# basketball_robot_main_board_2018.net
KiCad netlist of a schematic drawn in Altium Designer
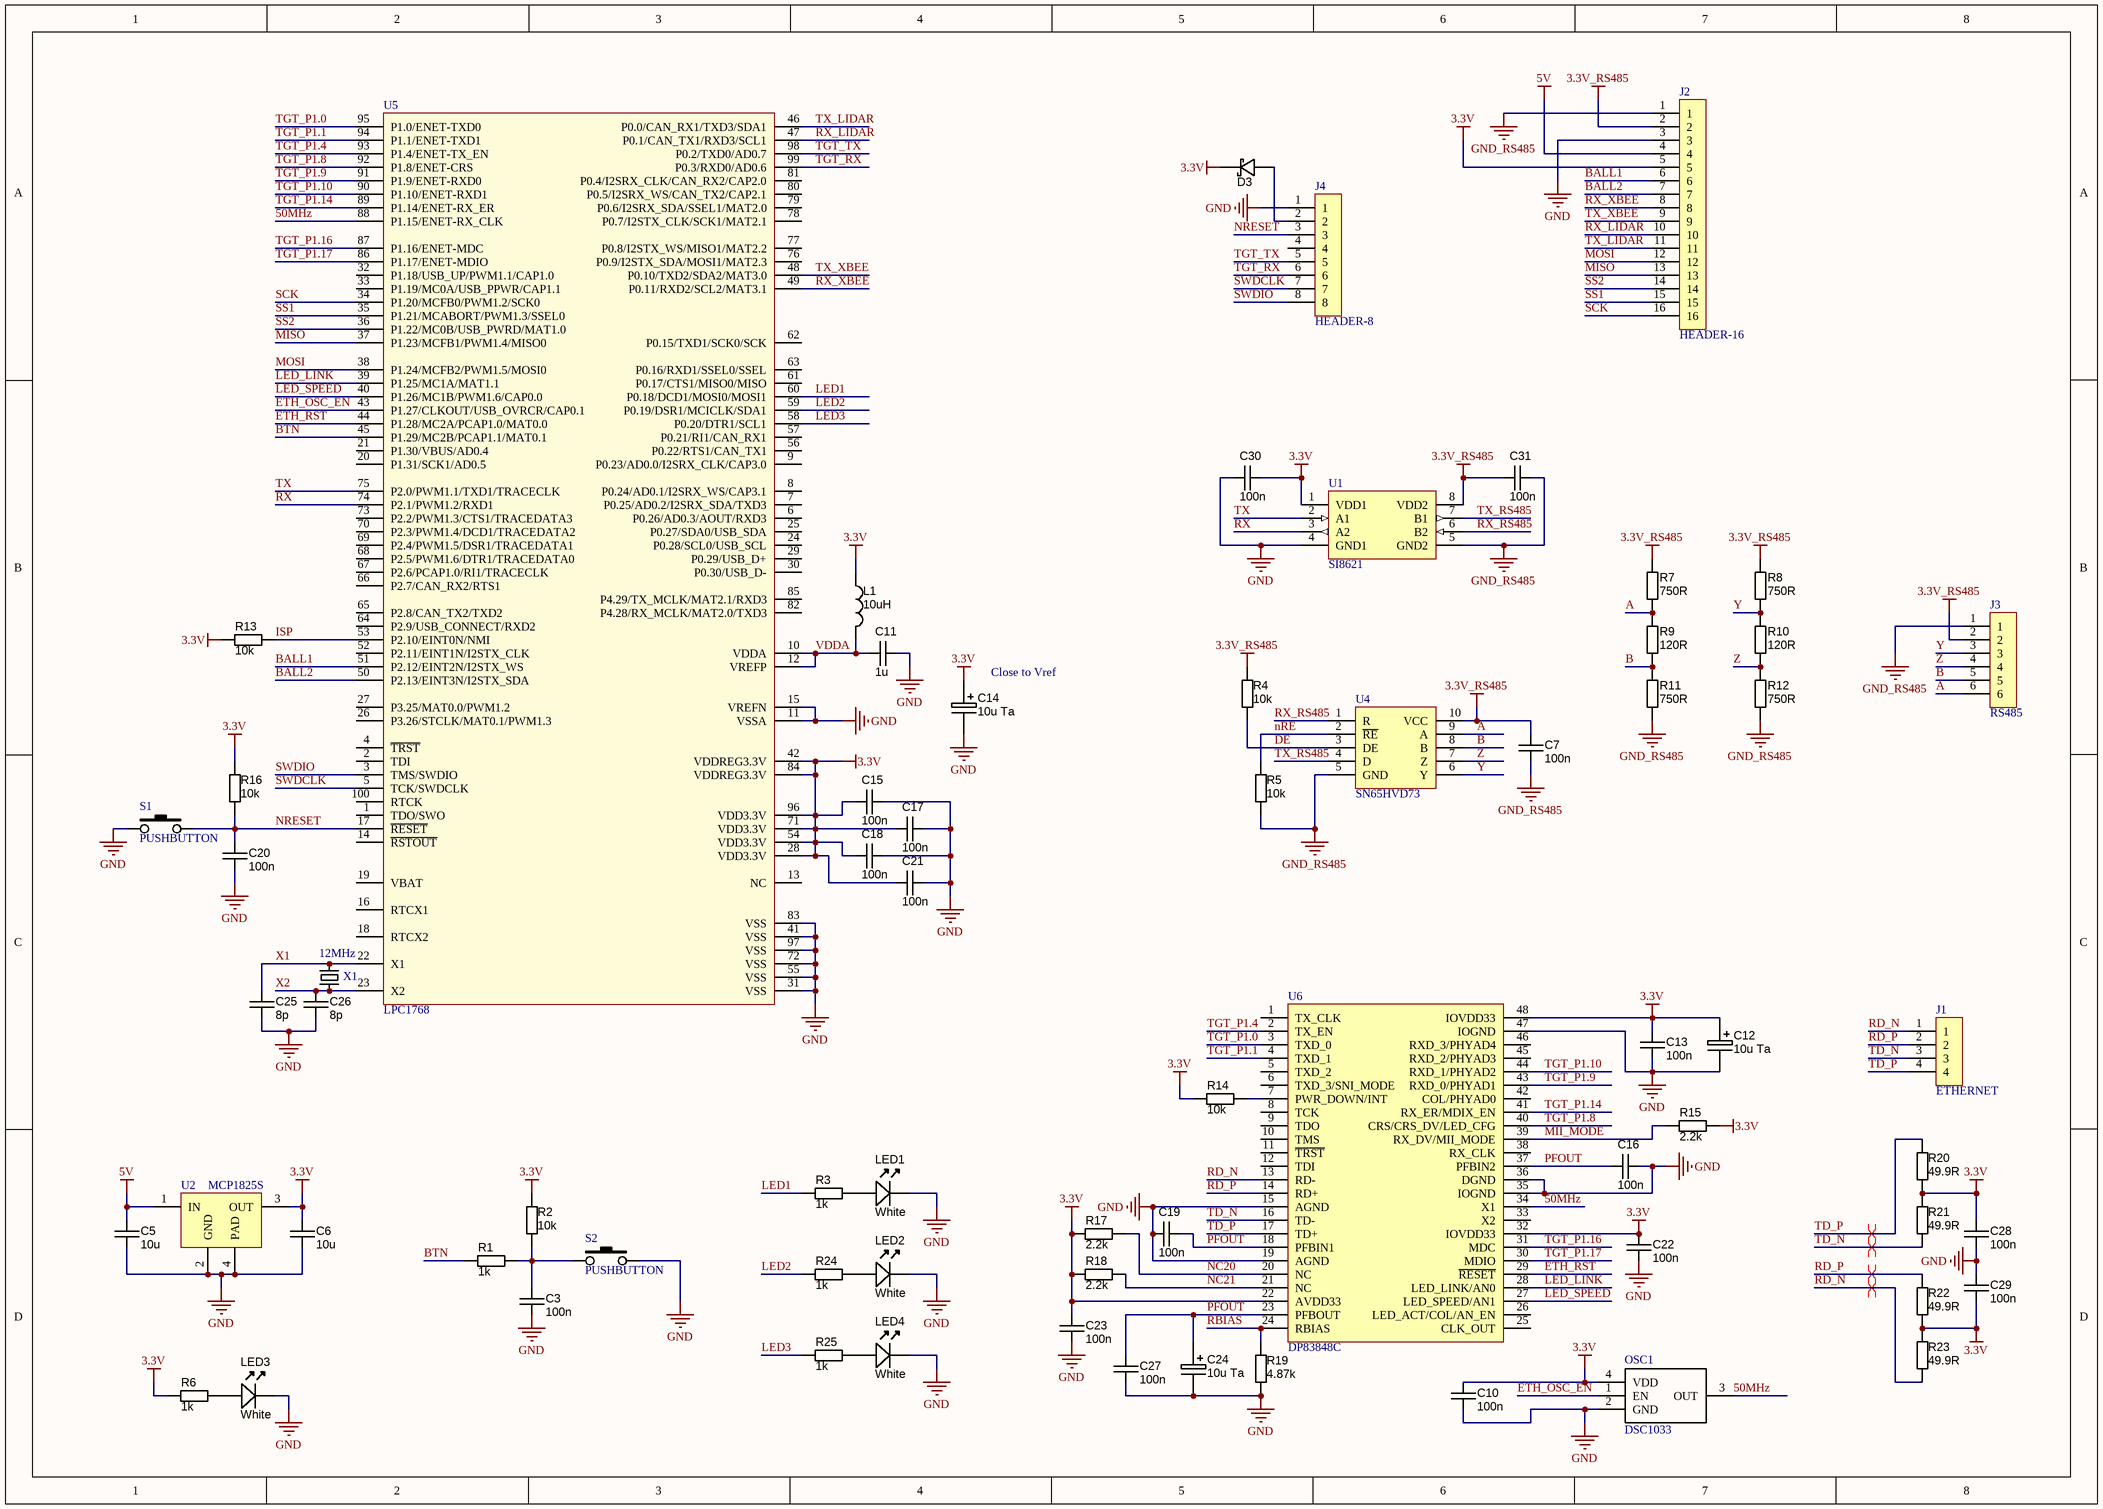
[diagram p0: basketball_robot_main_board_2018.SchDoc]

(export (version "E")
  (design (tool "Eeschema 10.0.6"))
  (components
    (comp (ref "C3")
      (value "100n")
      (footprint "CAPC1608X90N")
      (description "Capacitor SMD Cer 100nF 10% 50V X7R 0603")
      (fields (field (name "TOLERANCE") "±10%"))
      (libsource (lib "PBL - Capacitors") (part "CAPC_100n_0603_X7R_50V_10%"))
    )
    (comp (ref "C5")
      (value "10u")
      (footprint "CAPC3216X180N")
      (description "Capacitor SMD Cer 10uF 10% 10V X5R 1206")
      (fields (field (name "TOLERANCE") "±10%"))
      (libsource (lib "PBL - Capacitors") (part "CAPC_10u_1206_10V"))
    )
    (comp (ref "C6")
      (value "10u")
      (footprint "CAPC3216X180N")
      (description "Capacitor SMD Cer 10uF 10% 10V X5R 1206")
      (fields (field (name "TOLERANCE") "±10%"))
      (libsource (lib "PBL - Capacitors") (part "CAPC_10u_1206_10V"))
    )
    (comp (ref "C7")
      (value "100n")
      (footprint "CAPC1608X90N")
      (description "Capacitor SMD Cer 100nF 10% 50V X7R 0603")
      (fields (field (name "TOLERANCE") "±10%"))
      (libsource (lib "PBL - Capacitors") (part "CAPC_100n_0603_X7R_50V_10%"))
    )
    (comp (ref "C10")
      (value "100n")
      (footprint "CAPC1608X90N")
      (description "Capacitor SMD Cer 18pF 2% 100V NP0 0603")
      (fields (field (name "TOLERANCE") "±2%"))
      (libsource (lib "PBL - Capacitors") (part "CAPC_18p_0603_100V"))
    )
    (comp (ref "C11")
      (value "1u")
      (footprint "CAPC1608X90N")
      (description "Capacitor SMD Cer 1uF 10% 16V X7R 0603")
      (fields (field (name "TOLERANCE") "±10%"))
      (libsource (lib "PBL - Capacitors") (part "CAPC_1u_0603_X7R_16V_10%"))
    )
    (comp (ref "C12")
      (value "10u Ta")
      (footprint "CAPMP3528X210N")
      (description "Capacitor SMD Tantalum 47uF 20% 6.3V 1210")
      (fields (field (name "TOLERANCE") "±20%"))
      (libsource (lib "PBL - Capacitors") (part "CAPT_47u_1210_6V3"))
    )
    (comp (ref "C13")
      (value "100n")
      (footprint "CAPC1608X90N")
      (description "Capacitor SMD Cer 18pF 2% 100V NP0 0603")
      (fields (field (name "TOLERANCE") "±2%"))
      (libsource (lib "PBL - Capacitors") (part "CAPC_18p_0603_100V"))
    )
    (comp (ref "C14")
      (value "10u Ta")
      (footprint "CAPMP3528X210N")
      (description "Capacitor SMD Tantalum 47uF 20% 6.3V 1210")
      (fields (field (name "TOLERANCE") "±20%"))
      (libsource (lib "PBL - Capacitors") (part "CAPT_47u_1210_6V3"))
    )
    (comp (ref "C15")
      (value "100n")
      (footprint "CAPC1608X90N")
      (description "Capacitor SMD Cer 18pF 2% 100V NP0 0603")
      (fields (field (name "TOLERANCE") "±2%"))
      (libsource (lib "PBL - Capacitors") (part "CAPC_18p_0603_100V"))
    )
    (comp (ref "C16")
      (value "100n")
      (footprint "CAPC1608X90N")
      (description "Capacitor SMD Cer 18pF 2% 100V NP0 0603")
      (fields (field (name "TOLERANCE") "±2%"))
      (libsource (lib "PBL - Capacitors") (part "CAPC_18p_0603_100V"))
    )
    (comp (ref "C17")
      (value "100n")
      (footprint "CAPC1608X90N")
      (description "Capacitor SMD Cer 18pF 2% 100V NP0 0603")
      (fields (field (name "TOLERANCE") "±2%"))
      (libsource (lib "PBL - Capacitors") (part "CAPC_18p_0603_100V"))
    )
    (comp (ref "C18")
      (value "100n")
      (footprint "CAPC1608X90N")
      (description "Capacitor SMD Cer 18pF 2% 100V NP0 0603")
      (fields (field (name "TOLERANCE") "±2%"))
      (libsource (lib "PBL - Capacitors") (part "CAPC_18p_0603_100V"))
    )
    (comp (ref "C19")
      (value "100n")
      (footprint "CAPC1608X90N")
      (description "Capacitor SMD Cer 18pF 2% 100V NP0 0603")
      (fields (field (name "TOLERANCE") "±2%"))
      (libsource (lib "PBL - Capacitors") (part "CAPC_18p_0603_100V"))
    )
    (comp (ref "C20")
      (value "100n")
      (footprint "CAPC1608X90N")
      (description "Capacitor SMD Cer 18pF 2% 100V NP0 0603")
      (fields (field (name "TOLERANCE") "±2%"))
      (libsource (lib "PBL - Capacitors") (part "CAPC_18p_0603_100V"))
    )
    (comp (ref "C21")
      (value "100n")
      (footprint "CAPC1608X90N")
      (description "Capacitor SMD Cer 18pF 2% 100V NP0 0603")
      (fields (field (name "TOLERANCE") "±2%"))
      (libsource (lib "PBL - Capacitors") (part "CAPC_18p_0603_100V"))
    )
    (comp (ref "C22")
      (value "100n")
      (footprint "CAPC1608X90N")
      (description "Capacitor SMD Cer 18pF 2% 100V NP0 0603")
      (fields (field (name "TOLERANCE") "±2%"))
      (libsource (lib "PBL - Capacitors") (part "CAPC_18p_0603_100V"))
    )
    (comp (ref "C23")
      (value "100n")
      (footprint "CAPC1608X90N")
      (description "Capacitor SMD Cer 18pF 2% 100V NP0 0603")
      (fields (field (name "TOLERANCE") "±2%"))
      (libsource (lib "PBL - Capacitors") (part "CAPC_18p_0603_100V"))
    )
    (comp (ref "C24")
      (value "10u Ta")
      (footprint "CAPMP3528X210N")
      (description "Capacitor SMD Tantalum 47uF 20% 6.3V 1210")
      (fields (field (name "TOLERANCE") "±20%"))
      (libsource (lib "PBL - Capacitors") (part "CAPT_47u_1210_6V3"))
    )
    (comp (ref "C25")
      (value "8p")
      (footprint "CAPC1608X90N")
      (description "Capacitor SMD Cer 18pF 2% 100V NP0 0603")
      (fields (field (name "TOLERANCE") "±2%"))
      (libsource (lib "PBL - Capacitors") (part "CAPC_18p_0603_100V"))
    )
    (comp (ref "C26")
      (value "8p")
      (footprint "CAPC1608X90N")
      (description "Capacitor SMD Cer 18pF 2% 100V NP0 0603")
      (fields (field (name "TOLERANCE") "±2%"))
      (libsource (lib "PBL - Capacitors") (part "CAPC_18p_0603_100V"))
    )
    (comp (ref "C27")
      (value "100n")
      (footprint "CAPC1608X90N")
      (description "Capacitor SMD Cer 18pF 2% 100V NP0 0603")
      (fields (field (name "TOLERANCE") "±2%"))
      (libsource (lib "PBL - Capacitors") (part "CAPC_18p_0603_100V"))
    )
    (comp (ref "C28")
      (value "100n")
      (footprint "CAPC1608X90N")
      (description "Capacitor SMD Cer 18pF 2% 100V NP0 0603")
      (fields (field (name "TOLERANCE") "±2%"))
      (libsource (lib "PBL - Capacitors") (part "CAPC_18p_0603_100V"))
    )
    (comp (ref "C29")
      (value "100n")
      (footprint "CAPC1608X90N")
      (description "Capacitor SMD Cer 18pF 2% 100V NP0 0603")
      (fields (field (name "TOLERANCE") "±2%"))
      (libsource (lib "PBL - Capacitors") (part "CAPC_18p_0603_100V"))
    )
    (comp (ref "C30")
      (value "100n")
      (footprint "CAPC1608X90N")
      (description "Capacitor SMD Cer 100nF 10% 50V X7R 0603")
      (fields (field (name "TOLERANCE") "±10%"))
      (libsource (lib "PBL - Capacitors") (part "CAPC_100n_0603_X7R_50V_10%"))
    )
    (comp (ref "C31")
      (value "100n")
      (footprint "CAPC1608X90N")
      (description "Capacitor SMD Cer 100nF 10% 50V X7R 0603")
      (fields (field (name "TOLERANCE") "±10%"))
      (libsource (lib "PBL - Capacitors") (part "CAPC_100n_0603_X7R_50V_10%"))
    )
    (comp (ref "D3")
      (value "~")
      (footprint "SOD323")
      (description "Diode Schottky SMD 20V 0.5A SOD123")
      (libsource (lib "PBL - Diodes") (part "DIODE_SCHOTTKY_SS0520"))
    )
    (comp (ref "J1")
      (value "ETHERNET")
      (footprint "MICRO-MATCH-FOB-04")
      (libsource (lib "connectors_micromatch") (part "HEADER-4"))
    )
    (comp (ref "J2")
      (value "HEADER-16")
      (footprint "MICRO-MATCH-FOB-SMD-16")
      (libsource (lib "connectors_micromatch") (part "HEADER-16"))
    )
    (comp (ref "J3")
      (value "RS485")
      (footprint "MICRO-MATCH-FOB-06")
      (libsource (lib "connectors_micromatch") (part "HEADER-6"))
    )
    (comp (ref "J4")
      (value "HEADER-8")
      (footprint "MICRO-MATCH-FOB-SMD-08")
      (libsource (lib "connectors_micromatch") (part "HEADER-8"))
    )
    (comp (ref "L1")
      (value "10uH")
      (footprint "INDC1608N")
      (description "Ferrite bead 120 Ohm at 100 MHz 2A 0603 SMD")
      (libsource (lib "PBL - Inductors") (part "FERRITE_120R-100MHz_0603"))
    )
    (comp (ref "LED1")
      (value "White")
      (footprint "LED-0603-WHITE")
      (description "LED 0603 SMD Bright White 8700K")
      (libsource (lib "PBL - Light Sources") (part "LED_SMD_White_0603_Bright"))
    )
    (comp (ref "LED2")
      (value "White")
      (footprint "LED-0603-WHITE")
      (description "LED 0603 SMD Bright White 8700K")
      (libsource (lib "PBL - Light Sources") (part "LED_SMD_White_0603_Bright"))
    )
    (comp (ref "LED3")
      (value "White")
      (footprint "LED-0603-WHITE")
      (description "LED 0603 SMD Bright White 8700K")
      (libsource (lib "PBL - Light Sources") (part "LED_SMD_White_0603_Bright"))
    )
    (comp (ref "LED4")
      (value "White")
      (footprint "LED-0603-WHITE")
      (description "LED 0603 SMD Bright White 8700K")
      (libsource (lib "PBL - Light Sources") (part "LED_SMD_White_0603_Bright"))
    )
    (comp (ref "OSC1")
      (value "DSC1033")
      (footprint "DSC1033-3.2x2.5")
      (libsource (lib "misc") (part "DSC1033"))
    )
    (comp (ref "R1")
      (value "1k")
      (footprint "RESC1608X55N")
      (description "Resistor SMD chip 120 Ohm 0.1W 5% 0603")
      (fields (field (name "TOLERANCE") "±5%"))
      (libsource (lib "") (part "RES_120R_0603_5%_1"))
    )
    (comp (ref "R2")
      (value "10k")
      (footprint "RESC1608X55N")
      (description "Resistor SMD chip 120 Ohm 0.1W 5% 0603")
      (fields (field (name "TOLERANCE") "±5%"))
      (libsource (lib "") (part "RES_120R_0603_5%_2"))
    )
    (comp (ref "R3")
      (value "1k")
      (footprint "RESC1608X55N")
      (description "Resistor SMD chip 120 Ohm 0.1W 5% 0603")
      (fields (field (name "TOLERANCE") "±5%"))
      (libsource (lib "") (part "RES_120R_0603_5%_1"))
    )
    (comp (ref "R4")
      (value "10k")
      (footprint "RESC1608X55N")
      (description "Resistor SMD chip 120 Ohm 0.1W 5% 0603")
      (fields (field (name "TOLERANCE") "±5%"))
      (libsource (lib "") (part "RES_120R_0603_5%_2"))
    )
    (comp (ref "R5")
      (value "10k")
      (footprint "RESC1608X55N")
      (description "Resistor SMD chip 120 Ohm 0.1W 5% 0603")
      (fields (field (name "TOLERANCE") "±5%"))
      (libsource (lib "") (part "RES_120R_0603_5%_2"))
    )
    (comp (ref "R6")
      (value "1k")
      (footprint "RESC1608X55N")
      (description "Resistor SMD chip 120 Ohm 0.1W 5% 0603")
      (fields (field (name "TOLERANCE") "±5%"))
      (libsource (lib "") (part "RES_120R_0603_5%_1"))
    )
    (comp (ref "R7")
      (value "750R")
      (footprint "RESC1608X55N")
      (description "Resistor SMD chip 120 Ohm 0.1W 5% 0603")
      (fields (field (name "TOLERANCE") "±5%"))
      (libsource (lib "PBL - Resistors") (part "RES_120R_0603_5%"))
    )
    (comp (ref "R8")
      (value "750R")
      (footprint "RESC1608X55N")
      (description "Resistor SMD chip 120 Ohm 0.1W 5% 0603")
      (fields (field (name "TOLERANCE") "±5%"))
      (libsource (lib "PBL - Resistors") (part "RES_120R_0603_5%"))
    )
    (comp (ref "R9")
      (value "120R")
      (footprint "RESC1608X55N")
      (description "Resistor SMD chip 120 Ohm 0.1W 5% 0603")
      (fields (field (name "TOLERANCE") "±5%"))
      (libsource (lib "PBL - Resistors") (part "RES_120R_0603_5%"))
    )
    (comp (ref "R10")
      (value "120R")
      (footprint "RESC1608X55N")
      (description "Resistor SMD chip 120 Ohm 0.1W 5% 0603")
      (fields (field (name "TOLERANCE") "±5%"))
      (libsource (lib "PBL - Resistors") (part "RES_120R_0603_5%"))
    )
    (comp (ref "R11")
      (value "750R")
      (footprint "RESC1608X55N")
      (description "Resistor SMD chip 120 Ohm 0.1W 5% 0603")
      (fields (field (name "TOLERANCE") "±5%"))
      (libsource (lib "PBL - Resistors") (part "RES_120R_0603_5%"))
    )
    (comp (ref "R12")
      (value "750R")
      (footprint "RESC1608X55N")
      (description "Resistor SMD chip 120 Ohm 0.1W 5% 0603")
      (fields (field (name "TOLERANCE") "±5%"))
      (libsource (lib "PBL - Resistors") (part "RES_120R_0603_5%"))
    )
    (comp (ref "R13")
      (value "10k")
      (footprint "RESC1608X55N")
      (description "Resistor SMD chip 10k Ohm 0.1W 5% 0603")
      (fields (field (name "TOLERANCE") "±5%"))
      (libsource (lib "") (part "RES_10K_0603_5%_1"))
    )
    (comp (ref "R14")
      (value "10k")
      (footprint "RESC1608X55N")
      (description "Resistor SMD chip 10k Ohm 0.1W 5% 0603")
      (fields (field (name "TOLERANCE") "±5%"))
      (libsource (lib "") (part "RES_10K_0603_5%_1"))
    )
    (comp (ref "R15")
      (value "2.2k")
      (footprint "RESC1608X55N")
      (description "Resistor SMD chip 10k Ohm 0.1W 5% 0603")
      (fields (field (name "TOLERANCE") "±5%"))
      (libsource (lib "") (part "RES_10K_0603_5%_1"))
    )
    (comp (ref "R16")
      (value "10k")
      (footprint "RESC1608X55N")
      (description "Resistor SMD chip 10k Ohm 0.1W 5% 0603")
      (fields (field (name "TOLERANCE") "±5%"))
      (libsource (lib "PBL - Resistors") (part "RES_10K_0603_5%"))
    )
    (comp (ref "R17")
      (value "2.2k")
      (footprint "RESC1608X55N")
      (description "Resistor SMD chip 10k Ohm 0.1W 5% 0603")
      (fields (field (name "TOLERANCE") "±5%"))
      (libsource (lib "") (part "RES_10K_0603_5%_1"))
    )
    (comp (ref "R18")
      (value "2.2k")
      (footprint "RESC1608X55N")
      (description "Resistor SMD chip 10k Ohm 0.1W 5% 0603")
      (fields (field (name "TOLERANCE") "±5%"))
      (libsource (lib "") (part "RES_10K_0603_5%_1"))
    )
    (comp (ref "R19")
      (value "4.87k")
      (footprint "RESC1608X55N")
      (description "Resistor SMD chip 10k Ohm 0.1W 5% 0603")
      (fields (field (name "TOLERANCE") "±5%"))
      (libsource (lib "PBL - Resistors") (part "RES_10K_0603_5%"))
    )
    (comp (ref "R20")
      (value "49.9R")
      (footprint "RESC1608X55N")
      (description "Resistor SMD chip 10k Ohm 0.1W 5% 0603")
      (fields (field (name "TOLERANCE") "±5%"))
      (libsource (lib "PBL - Resistors") (part "RES_10K_0603_5%"))
    )
    (comp (ref "R21")
      (value "49.9R")
      (footprint "RESC1608X55N")
      (description "Resistor SMD chip 10k Ohm 0.1W 5% 0603")
      (fields (field (name "TOLERANCE") "±5%"))
      (libsource (lib "PBL - Resistors") (part "RES_10K_0603_5%"))
    )
    (comp (ref "R22")
      (value "49.9R")
      (footprint "RESC1608X55N")
      (description "Resistor SMD chip 10k Ohm 0.1W 5% 0603")
      (fields (field (name "TOLERANCE") "±5%"))
      (libsource (lib "PBL - Resistors") (part "RES_10K_0603_5%"))
    )
    (comp (ref "R23")
      (value "49.9R")
      (footprint "RESC1608X55N")
      (description "Resistor SMD chip 10k Ohm 0.1W 5% 0603")
      (fields (field (name "TOLERANCE") "±5%"))
      (libsource (lib "PBL - Resistors") (part "RES_10K_0603_5%"))
    )
    (comp (ref "R24")
      (value "1k")
      (footprint "RESC1608X55N")
      (description "Resistor SMD chip 120 Ohm 0.1W 5% 0603")
      (fields (field (name "TOLERANCE") "±5%"))
      (libsource (lib "") (part "RES_120R_0603_5%_1"))
    )
    (comp (ref "R25")
      (value "1k")
      (footprint "RESC1608X55N")
      (description "Resistor SMD chip 120 Ohm 0.1W 5% 0603")
      (fields (field (name "TOLERANCE") "±5%"))
      (libsource (lib "") (part "RES_120R_0603_5%_1"))
    )
    (comp (ref "S1")
      (value "PUSHBUTTON")
      (footprint "KMR421NGLFS")
      (libsource (lib "switches") (part "PUSHBUTTON"))
    )
    (comp (ref "S2")
      (value "PUSHBUTTON")
      (footprint "NKK_AB11AP-FA")
      (libsource (lib "switches") (part "PUSHBUTTON"))
    )
    (comp (ref "U1") (value "SI8621") (footprint "SOIC8") (libsource (lib "digital") (part "SI8621")))
    (comp (ref "U2")
      (value "MCP1825S")
      (footprint "SOT230P700X180-4N")
      (libsource (lib "power") (part "MIC5239"))
    )
    (comp (ref "U4")
      (value "SN65HVD73")
      (footprint "SOP10")
      (libsource (lib "texas_instruments") (part "SN65HVD3086E"))
    )
    (comp (ref "U5") (value "LPC1768") (footprint "LQFP100") (libsource (lib "nxp") (part "LPC1768")))
    (comp (ref "U6")
      (value "DP83848C")
      (footprint "PQFP48")
      (libsource (lib "texas_instruments") (part "DP83848C"))
    )
    (comp (ref "X1")
      (value "12MHz")
      (footprint "XTAL-3.2x2.5")
      (libsource (lib "misc") (part "XTAL-3.2X2.5"))
    )
  )
  (nets
    (net (code "1") (name "/50MHz") (class "Default")
      (node (ref "OSC1") (pin "3") (pinfunction "OUT_3") (pintype "passive"))
      (node (ref "U5") (pin "88") (pinfunction "P1.15/ENET-RX_CLK_88") (pintype "passive"))
      (node (ref "U6") (pin "34") (pinfunction "X1_34") (pintype "passive"))
    )
    (net (code "2") (name "/A") (class "Default")
      (node (ref "J3") (pin "6") (pinfunction "6_6") (pintype "passive"))
      (node (ref "R7") (pin "2") (pinfunction "2_2") (pintype "passive"))
      (node (ref "R9") (pin "1") (pinfunction "1_1") (pintype "passive"))
      (node (ref "U4") (pin "9") (pinfunction "A_9") (pintype "passive"))
    )
    (net (code "3") (name "/B") (class "Default")
      (node (ref "J3") (pin "5") (pinfunction "5_5") (pintype "passive"))
      (node (ref "R11") (pin "1") (pinfunction "1_1") (pintype "passive"))
      (node (ref "R9") (pin "2") (pinfunction "2_2") (pintype "passive"))
      (node (ref "U4") (pin "8") (pinfunction "B_8") (pintype "passive"))
    )
    (net (code "4") (name "/BALL1") (class "Default")
      (node (ref "J2") (pin "6") (pinfunction "6_6") (pintype "passive"))
      (node (ref "U5") (pin "51") (pinfunction "P2.12/EINT2N/I2STX_WS_51") (pintype "passive"))
    )
    (net (code "5") (name "/BALL2") (class "Default")
      (node (ref "J2") (pin "7") (pinfunction "7_7") (pintype "passive"))
      (node (ref "U5") (pin "50") (pinfunction "P2.13/EINT3N/I2STX_SDA_50") (pintype "passive"))
    )
    (net (code "6") (name "/BTN") (class "Default")
      (node (ref "R1") (pin "2") (pinfunction "2_2") (pintype "passive"))
      (node (ref "U5") (pin "45") (pinfunction "P1.29/MC2B/PCAP1.1/MAT0.1_45") (pintype "passive"))
    )
    (net (code "7") (name "/DE") (class "Default")
      (node (ref "R4") (pin "1") (pinfunction "1_1") (pintype "passive"))
      (node (ref "U4") (pin "3") (pinfunction "DE_3") (pintype "passive"))
    )
    (net (code "8") (name "/ETH_OSC_EN") (class "Default")
      (node (ref "OSC1") (pin "1") (pinfunction "EN_1") (pintype "passive"))
      (node (ref "U5") (pin "43") (pinfunction "P1.27/CLKOUT/USB_OVRCR/CAP0.1_43") (pintype "passive"))
    )
    (net (code "9") (name "/ETH_RST") (class "Default")
      (node (ref "U5") (pin "44") (pinfunction "P1.28/MC2A/PCAP1.0/MAT0.0_44") (pintype "passive"))
      (node (ref "U6") (pin "29") (pinfunction "~{RESET}_29") (pintype "passive"))
    )
    (net (code "10") (name "/ISP") (class "Default")
      (node (ref "R13") (pin "1") (pinfunction "1_1") (pintype "passive"))
      (node (ref "U5") (pin "53") (pinfunction "P2.10/EINT0N/NMI_53") (pintype "passive"))
    )
    (net (code "11") (name "/LED1") (class "Default")
      (node (ref "R3") (pin "2") (pinfunction "2_2") (pintype "passive"))
      (node (ref "U5") (pin "60") (pinfunction "P0.18/DCD1/MOSI0/MOSI1_60") (pintype "passive"))
    )
    (net (code "12") (name "/LED2") (class "Default")
      (node (ref "R24") (pin "2") (pinfunction "2_2") (pintype "passive"))
      (node (ref "U5") (pin "59") (pinfunction "P0.19/DSR1/MCICLK/SDA1_59") (pintype "passive"))
    )
    (net (code "13") (name "/LED3") (class "Default")
      (node (ref "R25") (pin "2") (pinfunction "2_2") (pintype "passive"))
      (node (ref "U5") (pin "58") (pinfunction "P0.20/DTR1/SCL1_58") (pintype "passive"))
    )
    (net (code "14") (name "/LED_LINK") (class "Default")
      (node (ref "U5") (pin "39") (pinfunction "P1.25/MC1A/MAT1.1_39") (pintype "passive"))
      (node (ref "U6") (pin "28") (pinfunction "LED_LINK/AN0_28") (pintype "passive"))
    )
    (net (code "15") (name "/LED_SPEED") (class "Default")
      (node (ref "U5") (pin "40") (pinfunction "P1.26/MC1B/PWM1.6/CAP0.0_40") (pintype "passive"))
      (node (ref "U6") (pin "27") (pinfunction "LED_SPEED/AN1_27") (pintype "passive"))
    )
    (net (code "16") (name "/MII_MODE") (class "Default")
      (node (ref "R15") (pin "2") (pinfunction "2_2") (pintype "passive"))
      (node (ref "U6") (pin "39") (pinfunction "RX_DV/MII_MODE_39") (pintype "passive"))
    )
    (net (code "17") (name "/MISO") (class "Default")
      (node (ref "J2") (pin "13") (pinfunction "13_13") (pintype "passive"))
      (node (ref "U5") (pin "37") (pinfunction "P1.23/MCFB1/PWM1.4/MISO0_37") (pintype "passive"))
    )
    (net (code "18") (name "/MOSI") (class "Default")
      (node (ref "J2") (pin "12") (pinfunction "12_12") (pintype "passive"))
      (node (ref "U5") (pin "38") (pinfunction "P1.24/MCFB2/PWM1.5/MOSI0_38") (pintype "passive"))
    )
    (net (code "19") (name "/NC20") (class "Default")
      (node (ref "R17") (pin "1") (pinfunction "1_1") (pintype "passive"))
      (node (ref "U6") (pin "20") (pinfunction "NC_20") (pintype "passive"))
    )
    (net (code "20") (name "/NC21") (class "Default")
      (node (ref "R18") (pin "1") (pinfunction "1_1") (pintype "passive"))
      (node (ref "U6") (pin "21") (pinfunction "NC_21") (pintype "passive"))
    )
    (net (code "21") (name "/NRESET") (class "Default")
      (node (ref "C20") (pin "1") (pintype "passive"))
      (node (ref "J4") (pin "3") (pinfunction "3_3") (pintype "passive"))
      (node (ref "R16") (pin "2") (pinfunction "2_2") (pintype "passive"))
      (node (ref "S1") (pin "2") (pintype "passive"))
      (node (ref "U5") (pin "17") (pinfunction "~{RESET}_17") (pintype "passive"))
    )
    (net (code "22") (name "/PFOUT") (class "Default")
      (node (ref "C16") (pin "1") (pintype "passive"))
      (node (ref "C19") (pin "2") (pintype "passive"))
      (node (ref "C24") (pin "1") (pintype "passive"))
      (node (ref "C27") (pin "2") (pintype "passive"))
      (node (ref "U6") (pin "18") (pinfunction "PFBIN1_18") (pintype "passive"))
      (node (ref "U6") (pin "23") (pinfunction "PFBOUT_23") (pintype "passive"))
      (node (ref "U6") (pin "37") (pinfunction "PFBIN2_37") (pintype "passive"))
    )
    (net (code "23") (name "/RBIAS") (class "Default")
      (node (ref "R19") (pin "1") (pinfunction "1_1") (pintype "passive"))
      (node (ref "U6") (pin "24") (pinfunction "RBIAS_24") (pintype "passive"))
    )
    (net (code "24") (name "/RD_N") (class "Default")
      (node (ref "J1") (pin "1") (pinfunction "1_1") (pintype "passive"))
      (node (ref "R23") (pin "2") (pinfunction "2_2") (pintype "passive"))
      (node (ref "U6") (pin "13") (pinfunction "RD-_13") (pintype "passive"))
    )
    (net (code "25") (name "/RD_P") (class "Default")
      (node (ref "J1") (pin "2") (pinfunction "2_2") (pintype "passive"))
      (node (ref "R22") (pin "1") (pinfunction "1_1") (pintype "passive"))
      (node (ref "U6") (pin "14") (pinfunction "RD+_14") (pintype "passive"))
    )
    (net (code "26") (name "/RX") (class "Default")
      (node (ref "U1") (pin "3") (pinfunction "A2_3") (pintype "output"))
      (node (ref "U5") (pin "74") (pinfunction "P2.1/PWM1.2/RXD1_74") (pintype "passive"))
    )
    (net (code "27") (name "/RX_LIDAR") (class "Default")
      (node (ref "J2") (pin "10") (pinfunction "10_10") (pintype "passive"))
      (node (ref "U5") (pin "47") (pinfunction "P0.1/CAN_TX1/RXD3/SCL1_47") (pintype "passive"))
    )
    (net (code "28") (name "/RX_RS485") (class "Default")
      (node (ref "U1") (pin "6") (pinfunction "B2_6") (pintype "input"))
      (node (ref "U4") (pin "1") (pinfunction "R_1") (pintype "passive"))
    )
    (net (code "29") (name "/RX_XBEE") (class "Default")
      (node (ref "J2") (pin "8") (pinfunction "8_8") (pintype "passive"))
      (node (ref "U5") (pin "49") (pinfunction "P0.11/RXD2/SCL2/MAT3.1_49") (pintype "passive"))
    )
    (net (code "30") (name "/SCK") (class "Default")
      (node (ref "J2") (pin "16") (pinfunction "16_16") (pintype "passive"))
      (node (ref "U5") (pin "34") (pinfunction "P1.20/MCFB0/PWM1.2/SCK0_34") (pintype "passive"))
    )
    (net (code "31") (name "/SS1") (class "Default")
      (node (ref "J2") (pin "15") (pinfunction "15_15") (pintype "passive"))
      (node (ref "U5") (pin "35") (pinfunction "P1.21/MCABORT/PWM1.3/SSEL0_35") (pintype "passive"))
    )
    (net (code "32") (name "/SS2") (class "Default")
      (node (ref "J2") (pin "14") (pinfunction "14_14") (pintype "passive"))
      (node (ref "U5") (pin "36") (pinfunction "P1.22/MC0B/USB_PWRD/MAT1.0_36") (pintype "passive"))
    )
    (net (code "33") (name "/SWDCLK") (class "Default")
      (node (ref "J4") (pin "7") (pinfunction "7_7") (pintype "passive"))
      (node (ref "U5") (pin "5") (pinfunction "TCK/SWDCLK_5") (pintype "passive"))
    )
    (net (code "34") (name "/SWDIO") (class "Default")
      (node (ref "J4") (pin "8") (pinfunction "8_8") (pintype "passive"))
      (node (ref "U5") (pin "3") (pinfunction "TMS/SWDIO_3") (pintype "passive"))
    )
    (net (code "35") (name "/TD_N") (class "Default")
      (node (ref "J1") (pin "3") (pinfunction "3_3") (pintype "passive"))
      (node (ref "R21") (pin "2") (pinfunction "2_2") (pintype "passive"))
      (node (ref "U6") (pin "16") (pinfunction "TD-_16") (pintype "passive"))
    )
    (net (code "36") (name "/TD_P") (class "Default")
      (node (ref "J1") (pin "4") (pinfunction "4_4") (pintype "passive"))
      (node (ref "R20") (pin "1") (pinfunction "1_1") (pintype "passive"))
      (node (ref "U6") (pin "17") (pinfunction "TD+_17") (pintype "passive"))
    )
    (net (code "37") (name "/TGT_P1.0") (class "Default")
      (node (ref "U5") (pin "95") (pinfunction "P1.0/ENET-TXD0_95") (pintype "passive"))
      (node (ref "U6") (pin "3") (pinfunction "TXD_0_3") (pintype "passive"))
    )
    (net (code "38") (name "/TGT_P1.1") (class "Default")
      (node (ref "U5") (pin "94") (pinfunction "P1.1/ENET-TXD1_94") (pintype "passive"))
      (node (ref "U6") (pin "4") (pinfunction "TXD_1_4") (pintype "passive"))
    )
    (net (code "39") (name "/TGT_P1.4") (class "Default")
      (node (ref "U5") (pin "93") (pinfunction "P1.4/ENET-TX_EN_93") (pintype "passive"))
      (node (ref "U6") (pin "2") (pinfunction "TX_EN_2") (pintype "passive"))
    )
    (net (code "40") (name "/TGT_P1.8") (class "Default")
      (node (ref "U5") (pin "92") (pinfunction "P1.8/ENET-CRS_92") (pintype "passive"))
      (node (ref "U6") (pin "40") (pinfunction "CRS/CRS_DV/LED_CFG_40") (pintype "passive"))
    )
    (net (code "41") (name "/TGT_P1.9") (class "Default")
      (node (ref "U5") (pin "91") (pinfunction "P1.9/ENET-RXD0_91") (pintype "passive"))
      (node (ref "U6") (pin "43") (pinfunction "RXD_0/PHYAD1_43") (pintype "passive"))
    )
    (net (code "42") (name "/TGT_P1.10") (class "Default")
      (node (ref "U5") (pin "90") (pinfunction "P1.10/ENET-RXD1_90") (pintype "passive"))
      (node (ref "U6") (pin "44") (pinfunction "RXD_1/PHYAD2_44") (pintype "passive"))
    )
    (net (code "43") (name "/TGT_P1.14") (class "Default")
      (node (ref "U5") (pin "89") (pinfunction "P1.14/ENET-RX_ER_89") (pintype "passive"))
      (node (ref "U6") (pin "41") (pinfunction "RX_ER/MDIX_EN_41") (pintype "passive"))
    )
    (net (code "44") (name "/TGT_P1.16") (class "Default")
      (node (ref "U5") (pin "87") (pinfunction "P1.16/ENET-MDC_87") (pintype "passive"))
      (node (ref "U6") (pin "31") (pinfunction "MDC_31") (pintype "passive"))
    )
    (net (code "45") (name "/TGT_P1.17") (class "Default")
      (node (ref "U5") (pin "86") (pinfunction "P1.17/ENET-MDIO_86") (pintype "passive"))
      (node (ref "U6") (pin "30") (pinfunction "MDIO_30") (pintype "passive"))
    )
    (net (code "46") (name "/TGT_RX") (class "Default")
      (node (ref "J4") (pin "6") (pinfunction "6_6") (pintype "passive"))
      (node (ref "U5") (pin "99") (pinfunction "P0.3/RXD0/AD0.6_99") (pintype "passive"))
    )
    (net (code "47") (name "/TGT_TX") (class "Default")
      (node (ref "J4") (pin "5") (pinfunction "5_5") (pintype "passive"))
      (node (ref "U5") (pin "98") (pinfunction "P0.2/TXD0/AD0.7_98") (pintype "passive"))
    )
    (net (code "48") (name "/TX") (class "Default")
      (node (ref "U1") (pin "2") (pinfunction "A1_2") (pintype "input"))
      (node (ref "U5") (pin "75") (pinfunction "P2.0/PWM1.1/TXD1/TRACECLK_75") (pintype "passive"))
    )
    (net (code "49") (name "/TX_LIDAR") (class "Default")
      (node (ref "J2") (pin "11") (pinfunction "11_11") (pintype "passive"))
      (node (ref "U5") (pin "46") (pinfunction "P0.0/CAN_RX1/TXD3/SDA1_46") (pintype "passive"))
    )
    (net (code "50") (name "/TX_RS485") (class "Default")
      (node (ref "U1") (pin "7") (pinfunction "B1_7") (pintype "output"))
      (node (ref "U4") (pin "4") (pinfunction "D_4") (pintype "passive"))
    )
    (net (code "51") (name "/TX_XBEE") (class "Default")
      (node (ref "J2") (pin "9") (pinfunction "9_9") (pintype "passive"))
      (node (ref "U5") (pin "48") (pinfunction "P0.10/TXD2/SDA2/MAT3.0_48") (pintype "passive"))
    )
    (net (code "52") (name "/VDDA") (class "Default")
      (node (ref "C11") (pin "1") (pintype "passive"))
      (node (ref "L1") (pin "2") (pinfunction "2_2") (pintype "passive"))
      (node (ref "U5") (pin "10") (pinfunction "VDDA_10") (pintype "passive"))
      (node (ref "U5") (pin "12") (pinfunction "VREFP_12") (pintype "passive"))
    )
    (net (code "53") (name "/X1") (class "Default")
      (node (ref "C25") (pin "1") (pintype "passive"))
      (node (ref "U5") (pin "22") (pinfunction "X1_22") (pintype "passive"))
      (node (ref "X1") (pin "3") (pinfunction "3_3") (pintype "passive"))
    )
    (net (code "54") (name "/X2") (class "Default")
      (node (ref "C26") (pin "1") (pintype "passive"))
      (node (ref "U5") (pin "23") (pinfunction "X2_23") (pintype "passive"))
      (node (ref "X1") (pin "1") (pinfunction "1_1") (pintype "passive"))
    )
    (net (code "55") (name "/Y") (class "Default")
      (node (ref "J3") (pin "3") (pinfunction "3_3") (pintype "passive"))
      (node (ref "R10") (pin "1") (pinfunction "1_1") (pintype "passive"))
      (node (ref "R8") (pin "2") (pinfunction "2_2") (pintype "passive"))
      (node (ref "U4") (pin "6") (pinfunction "Y_6") (pintype "passive"))
    )
    (net (code "56") (name "/Z") (class "Default")
      (node (ref "J3") (pin "4") (pinfunction "4_4") (pintype "passive"))
      (node (ref "R10") (pin "2") (pinfunction "2_2") (pintype "passive"))
      (node (ref "R12") (pin "1") (pinfunction "1_1") (pintype "passive"))
      (node (ref "U4") (pin "7") (pinfunction "Z_7") (pintype "passive"))
    )
    (net (code "57") (name "/nRE") (class "Default")
      (node (ref "R5") (pin "2") (pinfunction "2_2") (pintype "passive"))
      (node (ref "U4") (pin "2") (pinfunction "~{RE}_2") (pintype "passive"))
    )
    (net (code "58") (name "3.3V") (class "Default")
      (node (ref "C10") (pin "2") (pintype "passive"))
      (node (ref "C12") (pin "1") (pintype "passive"))
      (node (ref "C13") (pin "2") (pintype "passive"))
      (node (ref "C14") (pin "1") (pintype "passive"))
      (node (ref "C15") (pin "1") (pintype "passive"))
      (node (ref "C17") (pin "1") (pintype "passive"))
      (node (ref "C18") (pin "1") (pintype "passive"))
      (node (ref "C21") (pin "1") (pintype "passive"))
      (node (ref "C22") (pin "2") (pintype "passive"))
      (node (ref "C23") (pin "2") (pintype "passive"))
      (node (ref "C28") (pin "2") (pintype "passive"))
      (node (ref "C29") (pin "1") (pintype "passive"))
      (node (ref "C30") (pin "1") (pintype "passive"))
      (node (ref "C6") (pin "1") (pintype "passive"))
      (node (ref "D3") (pin "K") (pinfunction "K_K") (pintype "passive"))
      (node (ref "J2") (pin "5") (pinfunction "5_5") (pintype "passive"))
      (node (ref "L1") (pin "1") (pinfunction "1_1") (pintype "passive"))
      (node (ref "OSC1") (pin "4") (pinfunction "VDD_4") (pintype "passive"))
      (node (ref "R13") (pin "2") (pinfunction "2_2") (pintype "passive"))
      (node (ref "R14") (pin "2") (pinfunction "2_2") (pintype "passive"))
      (node (ref "R15") (pin "1") (pinfunction "1_1") (pintype "passive"))
      (node (ref "R16") (pin "1") (pinfunction "1_1") (pintype "passive"))
      (node (ref "R17") (pin "2") (pinfunction "2_2") (pintype "passive"))
      (node (ref "R18") (pin "2") (pinfunction "2_2") (pintype "passive"))
      (node (ref "R2") (pin "2") (pinfunction "2_2") (pintype "passive"))
      (node (ref "R20") (pin "2") (pinfunction "2_2") (pintype "passive"))
      (node (ref "R21") (pin "1") (pinfunction "1_1") (pintype "passive"))
      (node (ref "R22") (pin "2") (pinfunction "2_2") (pintype "passive"))
      (node (ref "R23") (pin "1") (pinfunction "1_1") (pintype "passive"))
      (node (ref "R6") (pin "2") (pinfunction "2_2") (pintype "passive"))
      (node (ref "U1") (pin "1") (pinfunction "VDD1_1") (pintype "passive"))
      (node (ref "U2") (pin "3") (pinfunction "OUT_3") (pintype "power_in"))
      (node (ref "U5") (pin "28") (pinfunction "VDD3.3V_28") (pintype "passive"))
      (node (ref "U5") (pin "42") (pinfunction "VDDREG3.3V_42") (pintype "passive"))
      (node (ref "U5") (pin "54") (pinfunction "VDD3.3V_54") (pintype "passive"))
      (node (ref "U5") (pin "71") (pinfunction "VDD3.3V_71") (pintype "passive"))
      (node (ref "U5") (pin "84") (pinfunction "VDDREG3.3V_84") (pintype "passive"))
      (node (ref "U5") (pin "96") (pinfunction "VDD3.3V_96") (pintype "passive"))
      (node (ref "U6") (pin "22") (pinfunction "AVDD33_22") (pintype "passive"))
      (node (ref "U6") (pin "32") (pinfunction "IOVDD33_32") (pintype "passive"))
      (node (ref "U6") (pin "48") (pinfunction "IOVDD33_48") (pintype "passive"))
    )
    (net (code "59") (name "3.3V_RS485") (class "Default")
      (node (ref "C31") (pin "2") (pintype "passive"))
      (node (ref "C7") (pin "1") (pintype "passive"))
      (node (ref "J2") (pin "2") (pinfunction "2_2") (pintype "passive"))
      (node (ref "J3") (pin "2") (pinfunction "2_2") (pintype "passive"))
      (node (ref "R4") (pin "2") (pinfunction "2_2") (pintype "passive"))
      (node (ref "R7") (pin "1") (pinfunction "1_1") (pintype "passive"))
      (node (ref "R8") (pin "1") (pinfunction "1_1") (pintype "passive"))
      (node (ref "U1") (pin "8") (pinfunction "VDD2_8") (pintype "passive"))
      (node (ref "U4") (pin "10") (pinfunction "VCC_10") (pintype "passive"))
    )
    (net (code "60") (name "5V") (class "Default")
      (node (ref "C5") (pin "1") (pintype "passive"))
      (node (ref "J2") (pin "4") (pinfunction "4_4") (pintype "passive"))
      (node (ref "U2") (pin "1") (pinfunction "IN_1") (pintype "power_in"))
    )
    (net (code "61") (name "GND") (class "Default")
      (node (ref "C10") (pin "1") (pintype "passive"))
      (node (ref "C11") (pin "2") (pintype "passive"))
      (node (ref "C12") (pin "2") (pintype "passive"))
      (node (ref "C13") (pin "1") (pintype "passive"))
      (node (ref "C14") (pin "2") (pintype "passive"))
      (node (ref "C15") (pin "2") (pintype "passive"))
      (node (ref "C16") (pin "2") (pintype "passive"))
      (node (ref "C17") (pin "2") (pintype "passive"))
      (node (ref "C18") (pin "2") (pintype "passive"))
      (node (ref "C19") (pin "1") (pintype "passive"))
      (node (ref "C20") (pin "2") (pintype "passive"))
      (node (ref "C21") (pin "2") (pintype "passive"))
      (node (ref "C22") (pin "1") (pintype "passive"))
      (node (ref "C23") (pin "1") (pintype "passive"))
      (node (ref "C24") (pin "2") (pintype "passive"))
      (node (ref "C25") (pin "2") (pintype "passive"))
      (node (ref "C26") (pin "2") (pintype "passive"))
      (node (ref "C27") (pin "1") (pintype "passive"))
      (node (ref "C28") (pin "1") (pintype "passive"))
      (node (ref "C29") (pin "2") (pintype "passive"))
      (node (ref "C3") (pin "2") (pintype "passive"))
      (node (ref "C30") (pin "2") (pintype "passive"))
      (node (ref "C5") (pin "2") (pintype "passive"))
      (node (ref "C6") (pin "2") (pintype "passive"))
      (node (ref "J2") (pin "3") (pinfunction "3_3") (pintype "passive"))
      (node (ref "J4") (pin "1") (pinfunction "1_1") (pintype "passive"))
      (node (ref "LED1") (pin "K") (pinfunction "K_K") (pintype "passive"))
      (node (ref "LED2") (pin "K") (pinfunction "K_K") (pintype "passive"))
      (node (ref "LED3") (pin "K") (pinfunction "K_K") (pintype "passive"))
      (node (ref "LED4") (pin "K") (pinfunction "K_K") (pintype "passive"))
      (node (ref "OSC1") (pin "2") (pinfunction "GND_2") (pintype "passive"))
      (node (ref "R19") (pin "2") (pinfunction "2_2") (pintype "passive"))
      (node (ref "S1") (pin "1") (pintype "passive"))
      (node (ref "S2") (pin "2") (pintype "passive"))
      (node (ref "U1") (pin "4") (pinfunction "GND1_4") (pintype "passive"))
      (node (ref "U2") (pin "2") (pinfunction "GND_2") (pintype "power_in"))
      (node (ref "U2") (pin "4") (pinfunction "PAD_4") (pintype "power_in"))
      (node (ref "U5") (pin "11") (pinfunction "VSSA_11") (pintype "passive"))
      (node (ref "U5") (pin "15") (pinfunction "VREFN_15") (pintype "passive"))
      (node (ref "U5") (pin "31") (pinfunction "VSS_31") (pintype "passive"))
      (node (ref "U5") (pin "41") (pinfunction "VSS_41") (pintype "passive"))
      (node (ref "U5") (pin "55") (pinfunction "VSS_55") (pintype "passive"))
      (node (ref "U5") (pin "72") (pinfunction "VSS_72") (pintype "passive"))
      (node (ref "U5") (pin "83") (pinfunction "VSS_83") (pintype "passive"))
      (node (ref "U5") (pin "97") (pinfunction "VSS_97") (pintype "passive"))
      (node (ref "U6") (pin "15") (pinfunction "AGND_15") (pintype "passive"))
      (node (ref "U6") (pin "19") (pinfunction "AGND_19") (pintype "passive"))
      (node (ref "U6") (pin "35") (pinfunction "IOGND_35") (pintype "passive"))
      (node (ref "U6") (pin "36") (pinfunction "DGND_36") (pintype "passive"))
      (node (ref "U6") (pin "47") (pinfunction "IOGND_47") (pintype "passive"))
    )
    (net (code "62") (name "GND_RS485") (class "Default")
      (node (ref "C31") (pin "1") (pintype "passive"))
      (node (ref "C7") (pin "2") (pintype "passive"))
      (node (ref "J2") (pin "1") (pinfunction "1_1") (pintype "passive"))
      (node (ref "J3") (pin "1") (pinfunction "1_1") (pintype "passive"))
      (node (ref "R11") (pin "2") (pinfunction "2_2") (pintype "passive"))
      (node (ref "R12") (pin "2") (pinfunction "2_2") (pintype "passive"))
      (node (ref "R5") (pin "1") (pinfunction "1_1") (pintype "passive"))
      (node (ref "U1") (pin "5") (pinfunction "GND2_5") (pintype "passive"))
      (node (ref "U4") (pin "5") (pinfunction "GND_5") (pintype "passive"))
    )
    (net (code "63") (name "Net-(C3-Pad1)") (class "Default")
      (node (ref "C3") (pin "1") (pintype "passive"))
      (node (ref "R1") (pin "1") (pinfunction "1_1") (pintype "passive"))
      (node (ref "R2") (pin "1") (pinfunction "1_1") (pintype "passive"))
      (node (ref "S2") (pin "1") (pintype "passive"))
    )
    (net (code "64") (name "Net-(D3-PadA)") (class "Default")
      (node (ref "D3") (pin "A") (pinfunction "A_A") (pintype "passive"))
      (node (ref "J4") (pin "2") (pinfunction "2_2") (pintype "passive"))
    )
    (net (code "65") (name "Net-(LED1-PadA)") (class "Default")
      (node (ref "LED1") (pin "A") (pinfunction "A_A") (pintype "passive"))
      (node (ref "R3") (pin "1") (pinfunction "1_1") (pintype "passive"))
    )
    (net (code "66") (name "Net-(LED2-PadA)") (class "Default")
      (node (ref "LED2") (pin "A") (pinfunction "A_A") (pintype "passive"))
      (node (ref "R24") (pin "1") (pinfunction "1_1") (pintype "passive"))
    )
    (net (code "67") (name "Net-(LED3-PadA)") (class "Default")
      (node (ref "LED3") (pin "A") (pinfunction "A_A") (pintype "passive"))
      (node (ref "R6") (pin "1") (pinfunction "1_1") (pintype "passive"))
    )
    (net (code "68") (name "Net-(LED4-PadA)") (class "Default")
      (node (ref "LED4") (pin "A") (pinfunction "A_A") (pintype "passive"))
      (node (ref "R25") (pin "1") (pinfunction "1_1") (pintype "passive"))
    )
    (net (code "69") (name "Net-(U6-PWR_DOWN{slash}INT)") (class "Default")
      (node (ref "R14") (pin "1") (pinfunction "1_1") (pintype "passive"))
      (node (ref "U6") (pin "7") (pinfunction "PWR_DOWN/INT_7") (pintype "passive"))
    )
    (net (code "70") (name "unconnected-(J4-Pad4)") (class "Default")
      (node (ref "J4") (pin "4") (pinfunction "4_4") (pintype "passive"))
    )
    (net (code "71") (name "unconnected-(U5-NC-Pad13)") (class "Default")
      (node (ref "U5") (pin "13") (pinfunction "NC_13") (pintype "passive"))
    )
    (net (code "72") (name "unconnected-(U5-P0.4{slash}I2SRX_CLK{slash}CAN_RX2{slash}CAP2.0-Pad81)") (class "Default")
      (node (ref "U5") (pin "81") (pinfunction "P0.4/I2SRX_CLK/CAN_RX2/CAP2.0_81") (pintype "passive"))
    )
    (net (code "73") (name "unconnected-(U5-P0.5{slash}I2SRX_WS{slash}CAN_TX2{slash}CAP2.1-Pad80)") (class "Default")
      (node (ref "U5") (pin "80") (pinfunction "P0.5/I2SRX_WS/CAN_TX2/CAP2.1_80") (pintype "passive"))
    )
    (net (code "74") (name "unconnected-(U5-P0.6{slash}I2SRX_SDA{slash}SSEL1{slash}MAT2.0-Pad79)") (class "Default")
      (node (ref "U5") (pin "79") (pinfunction "P0.6/I2SRX_SDA/SSEL1/MAT2.0_79") (pintype "passive"))
    )
    (net (code "75") (name "unconnected-(U5-P0.7{slash}I2STX_CLK{slash}SCK1{slash}MAT2.1-Pad78)") (class "Default")
      (node (ref "U5") (pin "78") (pinfunction "P0.7/I2STX_CLK/SCK1/MAT2.1_78") (pintype "passive"))
    )
    (net (code "76") (name "unconnected-(U5-P0.8{slash}I2STX_WS{slash}MISO1{slash}MAT2.2-Pad77)") (class "Default")
      (node (ref "U5") (pin "77") (pinfunction "P0.8/I2STX_WS/MISO1/MAT2.2_77") (pintype "passive"))
    )
    (net (code "77") (name "unconnected-(U5-P0.9{slash}I2STX_SDA{slash}MOSI1{slash}MAT2.3-Pad76)") (class "Default")
      (node (ref "U5") (pin "76") (pinfunction "P0.9/I2STX_SDA/MOSI1/MAT2.3_76") (pintype "passive"))
    )
    (net (code "78") (name "unconnected-(U5-P0.15{slash}TXD1{slash}SCK0{slash}SCK-Pad62)") (class "Default")
      (node (ref "U5") (pin "62") (pinfunction "P0.15/TXD1/SCK0/SCK_62") (pintype "passive"))
    )
    (net (code "79") (name "unconnected-(U5-P0.16{slash}RXD1{slash}SSEL0{slash}SSEL-Pad63)") (class "Default")
      (node (ref "U5") (pin "63") (pinfunction "P0.16/RXD1/SSEL0/SSEL_63") (pintype "passive"))
    )
    (net (code "80") (name "unconnected-(U5-P0.17{slash}CTS1{slash}MISO0{slash}MISO-Pad61)") (class "Default")
      (node (ref "U5") (pin "61") (pinfunction "P0.17/CTS1/MISO0/MISO_61") (pintype "passive"))
    )
    (net (code "81") (name "unconnected-(U5-P0.21{slash}RI1{slash}CAN_RX1-Pad57)") (class "Default")
      (node (ref "U5") (pin "57") (pinfunction "P0.21/RI1/CAN_RX1_57") (pintype "passive"))
    )
    (net (code "82") (name "unconnected-(U5-P0.22{slash}RTS1{slash}CAN_TX1-Pad56)") (class "Default")
      (node (ref "U5") (pin "56") (pinfunction "P0.22/RTS1/CAN_TX1_56") (pintype "passive"))
    )
    (net (code "83") (name "unconnected-(U5-P0.23{slash}AD0.0{slash}I2SRX_CLK{slash}CAP3.0-Pad9)") (class "Default")
      (node (ref "U5") (pin "9") (pinfunction "P0.23/AD0.0/I2SRX_CLK/CAP3.0_9") (pintype "passive"))
    )
    (net (code "84") (name "unconnected-(U5-P0.24{slash}AD0.1{slash}I2SRX_WS{slash}CAP3.1-Pad8)") (class "Default")
      (node (ref "U5") (pin "8") (pinfunction "P0.24/AD0.1/I2SRX_WS/CAP3.1_8") (pintype "passive"))
    )
    (net (code "85") (name "unconnected-(U5-P0.25{slash}AD0.2{slash}I2SRX_SDA{slash}TXD3-Pad7)") (class "Default")
      (node (ref "U5") (pin "7") (pinfunction "P0.25/AD0.2/I2SRX_SDA/TXD3_7") (pintype "passive"))
    )
    (net (code "86") (name "unconnected-(U5-P0.26{slash}AD0.3{slash}AOUT{slash}RXD3-Pad6)") (class "Default")
      (node (ref "U5") (pin "6") (pinfunction "P0.26/AD0.3/AOUT/RXD3_6") (pintype "passive"))
    )
    (net (code "87") (name "unconnected-(U5-P0.27{slash}SDA0{slash}USB_SDA-Pad25)") (class "Default")
      (node (ref "U5") (pin "25") (pinfunction "P0.27/SDA0/USB_SDA_25") (pintype "passive"))
    )
    (net (code "88") (name "unconnected-(U5-P0.28{slash}SCL0{slash}USB_SCL-Pad24)") (class "Default")
      (node (ref "U5") (pin "24") (pinfunction "P0.28/SCL0/USB_SCL_24") (pintype "passive"))
    )
    (net (code "89") (name "unconnected-(U5-P0.29{slash}USB_D+-Pad29)") (class "Default")
      (node (ref "U5") (pin "29") (pinfunction "P0.29/USB_D+_29") (pintype "passive"))
    )
    (net (code "90") (name "unconnected-(U5-P0.30{slash}USB_D--Pad30)") (class "Default")
      (node (ref "U5") (pin "30") (pinfunction "P0.30/USB_D-_30") (pintype "passive"))
    )
    (net (code "91") (name "unconnected-(U5-P1.18{slash}USB_UP{slash}PWM1.1{slash}CAP1.0-Pad32)") (class "Default")
      (node (ref "U5") (pin "32") (pinfunction "P1.18/USB_UP/PWM1.1/CAP1.0_32") (pintype "passive"))
    )
    (net (code "92") (name "unconnected-(U5-P1.19{slash}MC0A{slash}USB_PPWR{slash}CAP1.1-Pad33)") (class "Default")
      (node (ref "U5") (pin "33") (pinfunction "P1.19/MC0A/USB_PPWR/CAP1.1_33") (pintype "passive"))
    )
    (net (code "93") (name "unconnected-(U5-P1.30{slash}VBUS{slash}AD0.4-Pad21)") (class "Default")
      (node (ref "U5") (pin "21") (pinfunction "P1.30/VBUS/AD0.4_21") (pintype "passive"))
    )
    (net (code "94") (name "unconnected-(U5-P1.31{slash}SCK1{slash}AD0.5-Pad20)") (class "Default")
      (node (ref "U5") (pin "20") (pinfunction "P1.31/SCK1/AD0.5_20") (pintype "passive"))
    )
    (net (code "95") (name "unconnected-(U5-P2.2{slash}PWM1.3{slash}CTS1{slash}TRACEDATA3-Pad73)") (class "Default")
      (node (ref "U5") (pin "73") (pinfunction "P2.2/PWM1.3/CTS1/TRACEDATA3_73") (pintype "passive"))
    )
    (net (code "96") (name "unconnected-(U5-P2.3{slash}PWM1.4{slash}DCD1{slash}TRACEDATA2-Pad70)") (class "Default")
      (node (ref "U5") (pin "70") (pinfunction "P2.3/PWM1.4/DCD1/TRACEDATA2_70") (pintype "passive"))
    )
    (net (code "97") (name "unconnected-(U5-P2.4{slash}PWM1.5{slash}DSR1{slash}TRACEDATA1-Pad69)") (class "Default")
      (node (ref "U5") (pin "69") (pinfunction "P2.4/PWM1.5/DSR1/TRACEDATA1_69") (pintype "passive"))
    )
    (net (code "98") (name "unconnected-(U5-P2.5{slash}PWM1.6{slash}DTR1{slash}TRACEDATA0-Pad68)") (class "Default")
      (node (ref "U5") (pin "68") (pinfunction "P2.5/PWM1.6/DTR1/TRACEDATA0_68") (pintype "passive"))
    )
    (net (code "99") (name "unconnected-(U5-P2.6{slash}PCAP1.0{slash}RI1{slash}TRACECLK-Pad67)") (class "Default")
      (node (ref "U5") (pin "67") (pinfunction "P2.6/PCAP1.0/RI1/TRACECLK_67") (pintype "passive"))
    )
    (net (code "100") (name "unconnected-(U5-P2.7{slash}CAN_RX2{slash}RTS1-Pad66)") (class "Default")
      (node (ref "U5") (pin "66") (pinfunction "P2.7/CAN_RX2/RTS1_66") (pintype "passive"))
    )
    (net (code "101") (name "unconnected-(U5-P2.8{slash}CAN_TX2{slash}TXD2-Pad65)") (class "Default")
      (node (ref "U5") (pin "65") (pinfunction "P2.8/CAN_TX2/TXD2_65") (pintype "passive"))
    )
    (net (code "102") (name "unconnected-(U5-P2.9{slash}USB_CONNECT{slash}RXD2-Pad64)") (class "Default")
      (node (ref "U5") (pin "64") (pinfunction "P2.9/USB_CONNECT/RXD2_64") (pintype "passive"))
    )
    (net (code "103") (name "unconnected-(U5-P2.11{slash}EINT1N{slash}I2STX_CLK-Pad52)") (class "Default")
      (node (ref "U5") (pin "52") (pinfunction "P2.11/EINT1N/I2STX_CLK_52") (pintype "passive"))
    )
    (net (code "104") (name "unconnected-(U5-P3.25{slash}MAT0.0{slash}PWM1.2-Pad27)") (class "Default")
      (node (ref "U5") (pin "27") (pinfunction "P3.25/MAT0.0/PWM1.2_27") (pintype "passive"))
    )
    (net (code "105") (name "unconnected-(U5-P3.26{slash}STCLK{slash}MAT0.1{slash}PWM1.3-Pad26)") (class "Default")
      (node (ref "U5") (pin "26") (pinfunction "P3.26/STCLK/MAT0.1/PWM1.3_26") (pintype "passive"))
    )
    (net (code "106") (name "unconnected-(U5-P4.28{slash}RX_MCLK{slash}MAT2.0{slash}TXD3-Pad82)") (class "Default")
      (node (ref "U5") (pin "82") (pinfunction "P4.28/RX_MCLK/MAT2.0/TXD3_82") (pintype "passive"))
    )
    (net (code "107") (name "unconnected-(U5-P4.29{slash}TX_MCLK{slash}MAT2.1{slash}RXD3-Pad85)") (class "Default")
      (node (ref "U5") (pin "85") (pinfunction "P4.29/TX_MCLK/MAT2.1/RXD3_85") (pintype "passive"))
    )
    (net (code "108") (name "unconnected-(U5-RTCK-Pad100)") (class "Default")
      (node (ref "U5") (pin "100") (pinfunction "RTCK_100") (pintype "passive"))
    )
    (net (code "109") (name "unconnected-(U5-RTCX1-Pad16)") (class "Default")
      (node (ref "U5") (pin "16") (pinfunction "RTCX1_16") (pintype "passive"))
    )
    (net (code "110") (name "unconnected-(U5-RTCX2-Pad18)") (class "Default")
      (node (ref "U5") (pin "18") (pinfunction "RTCX2_18") (pintype "passive"))
    )
    (net (code "111") (name "unconnected-(U5-TDI-Pad2)") (class "Default")
      (node (ref "U5") (pin "2") (pinfunction "TDI_2") (pintype "passive"))
    )
    (net (code "112") (name "unconnected-(U5-TDO{slash}SWO-Pad1)") (class "Default")
      (node (ref "U5") (pin "1") (pinfunction "TDO/SWO_1") (pintype "passive"))
    )
    (net (code "113") (name "unconnected-(U5-VBAT-Pad19)") (class "Default")
      (node (ref "U5") (pin "19") (pinfunction "VBAT_19") (pintype "passive"))
    )
    (net (code "114") (name "unconnected-(U5-~{RSTOUT}-Pad14)") (class "Default")
      (node (ref "U5") (pin "14") (pinfunction "~{RSTOUT}_14") (pintype "passive"))
    )
    (net (code "115") (name "unconnected-(U5-~{TRST}-Pad4)") (class "Default")
      (node (ref "U5") (pin "4") (pinfunction "~{TRST}_4") (pintype "passive"))
    )
    (net (code "116") (name "unconnected-(U6-CLK_OUT-Pad25)") (class "Default")
      (node (ref "U6") (pin "25") (pinfunction "CLK_OUT_25") (pintype "passive"))
    )
    (net (code "117") (name "unconnected-(U6-COL{slash}PHYAD0-Pad42)") (class "Default")
      (node (ref "U6") (pin "42") (pinfunction "COL/PHYAD0_42") (pintype "passive"))
    )
    (net (code "118") (name "unconnected-(U6-LED_ACT{slash}COL{slash}AN_EN-Pad26)") (class "Default")
      (node (ref "U6") (pin "26") (pinfunction "LED_ACT/COL/AN_EN_26") (pintype "passive"))
    )
    (net (code "119") (name "unconnected-(U6-RXD_2{slash}PHYAD3-Pad45)") (class "Default")
      (node (ref "U6") (pin "45") (pinfunction "RXD_2/PHYAD3_45") (pintype "passive"))
    )
    (net (code "120") (name "unconnected-(U6-RXD_3{slash}PHYAD4-Pad46)") (class "Default")
      (node (ref "U6") (pin "46") (pinfunction "RXD_3/PHYAD4_46") (pintype "passive"))
    )
    (net (code "121") (name "unconnected-(U6-RX_CLK-Pad38)") (class "Default")
      (node (ref "U6") (pin "38") (pinfunction "RX_CLK_38") (pintype "passive"))
    )
    (net (code "122") (name "unconnected-(U6-TCK-Pad8)") (class "Default")
      (node (ref "U6") (pin "8") (pinfunction "TCK_8") (pintype "passive"))
    )
    (net (code "123") (name "unconnected-(U6-TDI-Pad12)") (class "Default")
      (node (ref "U6") (pin "12") (pinfunction "TDI_12") (pintype "passive"))
    )
    (net (code "124") (name "unconnected-(U6-TDO-Pad9)") (class "Default")
      (node (ref "U6") (pin "9") (pinfunction "TDO_9") (pintype "passive"))
    )
    (net (code "125") (name "unconnected-(U6-TMS-Pad10)") (class "Default")
      (node (ref "U6") (pin "10") (pinfunction "TMS_10") (pintype "passive"))
    )
    (net (code "126") (name "unconnected-(U6-TXD_2-Pad5)") (class "Default")
      (node (ref "U6") (pin "5") (pinfunction "TXD_2_5") (pintype "passive"))
    )
    (net (code "127") (name "unconnected-(U6-TXD_3{slash}SNI_MODE-Pad6)") (class "Default")
      (node (ref "U6") (pin "6") (pinfunction "TXD_3/SNI_MODE_6") (pintype "passive"))
    )
    (net (code "128") (name "unconnected-(U6-TX_CLK-Pad1)") (class "Default")
      (node (ref "U6") (pin "1") (pinfunction "TX_CLK_1") (pintype "passive"))
    )
    (net (code "129") (name "unconnected-(U6-X2-Pad33)") (class "Default")
      (node (ref "U6") (pin "33") (pinfunction "X2_33") (pintype "passive"))
    )
    (net (code "130") (name "unconnected-(U6-~{TRST}-Pad11)") (class "Default")
      (node (ref "U6") (pin "11") (pinfunction "~{TRST}_11") (pintype "passive"))
    )
  )
)
